# MicroController.net
KiCad netlist of a schematic drawn in Altium Designer
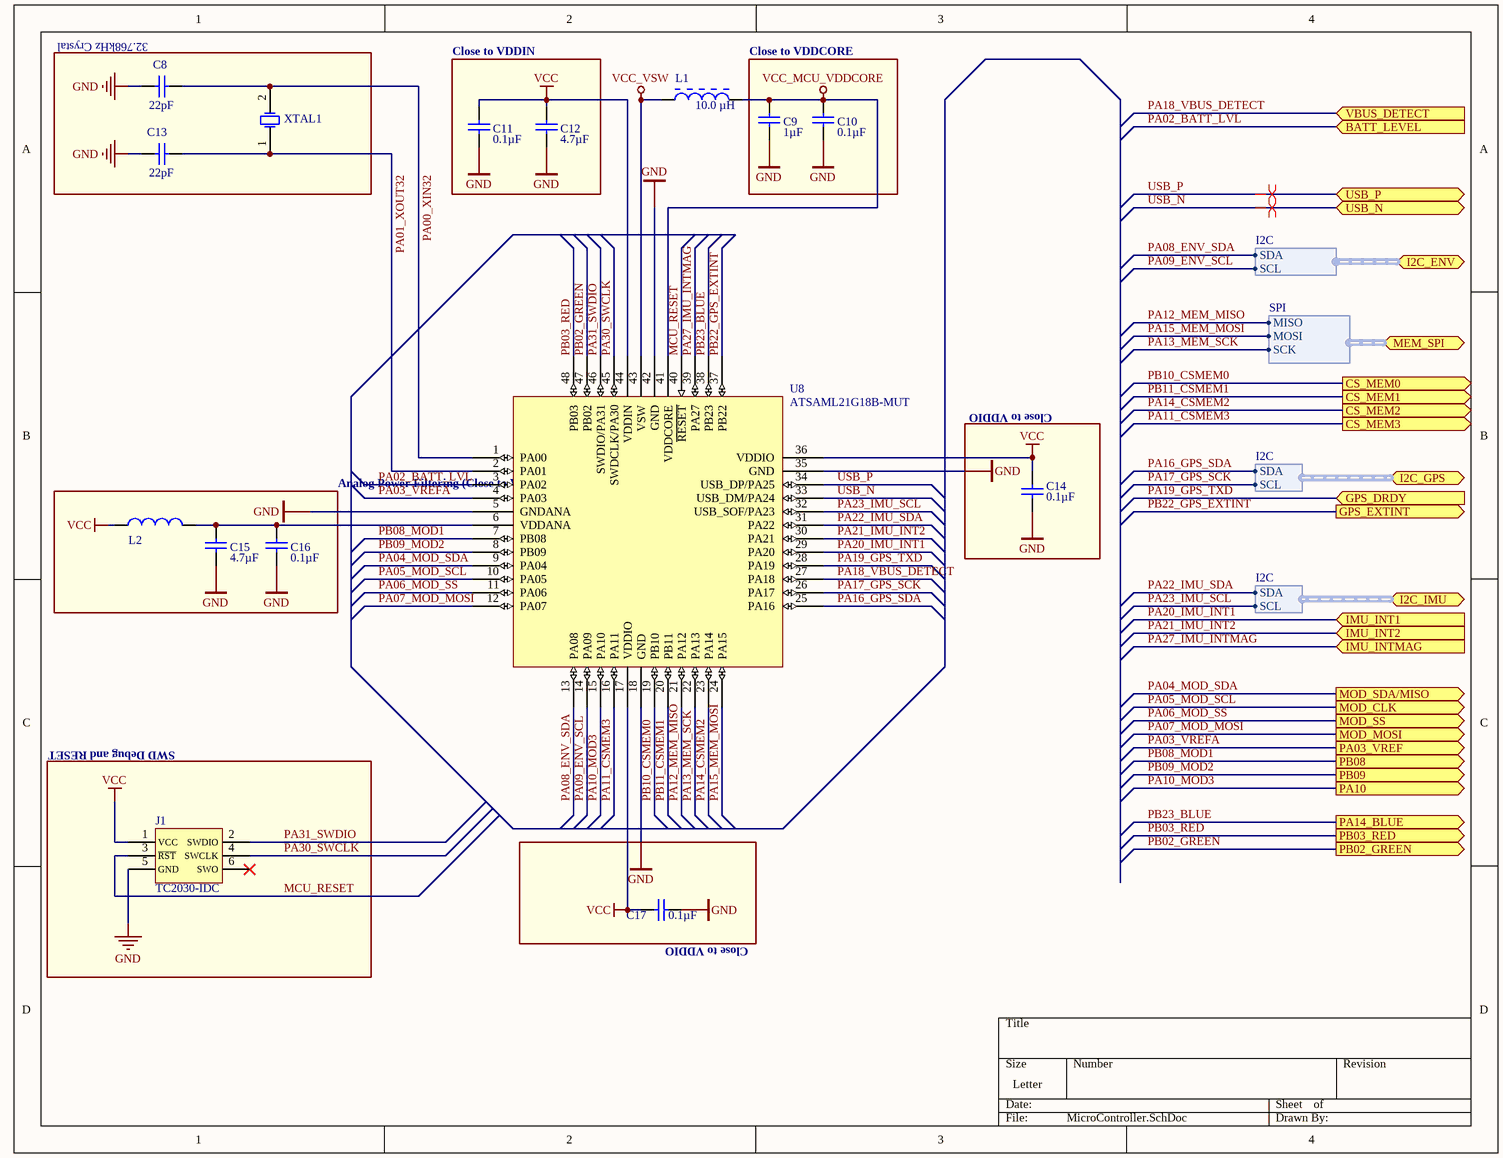
[diagram p0: MicroController.SchDoc]

(export (version "E")
  (design (tool "Eeschema 10.0.6"))
  (components
    (comp (ref "C8")
      (value "GRM1555C1H220FA01D")
      (footprint "C0402M")
      (description "CAP CER 22PF 50V C0G/NP0 0402")
      (fields
        (field (name "HOUSEPART") "NO")
        (field (name "TOLERANCE") "±1%")
        (field (name "CAPACITANCE") "22pF")
      )
      (libsource (lib "MF_Passives") (part "CAPACITOR_NP"))
    )
    (comp (ref "C9")
      (value "CL10B105KP8NFNC")
      (footprint "C0603N")
      (description "CAP CER 1UF 10V X7R 0603")
      (fields
        (field (name "HOUSEPART") "NO")
        (field (name "TOLERANCE") "±10%")
        (field (name "CAPACITANCE") "1µF")
      )
      (libsource (lib "MF_Passives") (part "CAPACITOR_NP"))
    )
    (comp (ref "C10")
      (value "CL10B104KO8NFNC")
      (footprint "C0603N")
      (fields
        (field (name "HOUSEPART") "NO")
        (field (name "TOLERANCE") "±10%")
        (field (name "VOLTAGE") "16V")
        (field (name "CAPACITANCE") "0.1µF")
      )
      (libsource (lib "MF_Passives") (part "CAPACITOR_NP"))
    )
    (comp (ref "C11")
      (value "CL10B104KO8NFNC")
      (footprint "C0603N")
      (fields
        (field (name "HOUSEPART") "NO")
        (field (name "TOLERANCE") "±10%")
        (field (name "VOLTAGE") "16V")
        (field (name "CAPACITANCE") "0.1µF")
      )
      (libsource (lib "MF_Passives") (part "CAPACITOR_NP"))
    )
    (comp (ref "C12")
      (value "C0603C475K8PACTU")
      (footprint "C0603N")
      (description "CAP CER 1UF 10V X7R 0603")
      (fields
        (field (name "HOUSEPART") "NO")
        (field (name "TOLERANCE") "±10%")
        (field (name "CAPACITANCE") "4.7µF")
      )
      (libsource (lib "MF_Passives") (part "CAPACITOR_NP"))
    )
    (comp (ref "C13")
      (value "GRM1555C1H220FA01D")
      (footprint "C0402M")
      (description "CAP CER 22PF 50V C0G/NP0 0402")
      (fields
        (field (name "HOUSEPART") "NO")
        (field (name "TOLERANCE") "±1%")
        (field (name "CAPACITANCE") "22pF")
      )
      (libsource (lib "MF_Passives") (part "CAPACITOR_NP"))
    )
    (comp (ref "C14")
      (value "CL10B104KO8NFNC")
      (footprint "C0603N")
      (fields
        (field (name "HOUSEPART") "NO")
        (field (name "TOLERANCE") "±10%")
        (field (name "VOLTAGE") "16V")
        (field (name "CAPACITANCE") "0.1µF")
      )
      (libsource (lib "MF_Passives") (part "CAPACITOR_NP"))
    )
    (comp (ref "C15")
      (value "C0603C475K8PACTU")
      (footprint "C0603N")
      (description "CAP CER 1UF 10V X7R 0603")
      (fields
        (field (name "HOUSEPART") "NO")
        (field (name "TOLERANCE") "±10%")
        (field (name "CAPACITANCE") "4.7µF")
      )
      (libsource (lib "MF_Passives") (part "CAPACITOR_NP"))
    )
    (comp (ref "C16")
      (value "CL10B104KO8NFNC")
      (footprint "C0603N")
      (fields
        (field (name "HOUSEPART") "NO")
        (field (name "TOLERANCE") "±10%")
        (field (name "VOLTAGE") "16V")
        (field (name "CAPACITANCE") "0.1µF")
      )
      (libsource (lib "MF_Passives") (part "CAPACITOR_NP"))
    )
    (comp (ref "C17")
      (value "CL10B104KO8NFNC")
      (footprint "C0603N")
      (fields
        (field (name "HOUSEPART") "NO")
        (field (name "TOLERANCE") "±10%")
        (field (name "VOLTAGE") "16V")
        (field (name "CAPACITANCE") "0.1µF")
      )
      (libsource (lib "MF_Passives") (part "CAPACITOR_NP"))
    )
    (comp (ref "J1")
      (value "TC2030-IDC")
      (footprint "PINHEAD127_1x5")
      (description "CABLE ADAPTER 6 POS")
      (fields (field (name "MANUFACTURER") "Tag-Connect LLC"))
      (libsource (lib "Connectors") (part "TC2030-IDC-NL"))
    )
    (comp (ref "L1")
      (value "SRN3015-100M")
      (footprint "SRN3015")
      (fields (field (name "INDUCTANCE") "10.0 µH"))
      (libsource (lib "Bourns") (part "CMP-911278-2"))
    )
    (comp (ref "L2")
      (value "LI0603G221R-10")
      (footprint "R0603L")
      (fields (field (name "HOUSEPART") "NO"))
      (libsource (lib "MF_Passives") (part "INDUCTOR"))
    )
    (comp (ref "U8")
      (value "ATSAML21G18B-MUT")
      (footprint "QFN50P700X700X90-49N")
      (libsource (lib "Microchip") (part "ATSAML21G18B-MUT"))
    )
    (comp (ref "XTAL1")
      (value "FC-135 32.7680KA-A3")
      (footprint "FC-135R$2F$FC-135")
      (description "FC-135 Series 32.768 KHz ±20 ppm 12.5 pF -40 to +85°C Surface Mount Crystal")
      (fields (field (name "MANUFACTURER") "epson"))
      (libsource (lib "FC-135R_RC-135") (part "FC-13532.7680KA-A3"))
    )
  )
  (nets
    (net (code "3") (name "/MCU_RESET") (class "Default")
      (node (ref "J1") (pin "3") (pinfunction "~{RST}_3") (pintype "passive"))
      (node (ref "U8") (pin "40") (pinfunction "~{RESET}_40") (pintype "input"))
    )
    (net (code "4") (name "/PA00_XIN32") (class "Default")
      (node (ref "C8") (pin "1") (pinfunction "1_1") (pintype "passive"))
      (node (ref "U8") (pin "1") (pinfunction "PA00_1") (pintype "bidirectional"))
      (node (ref "XTAL1") (pin "2") (pinfunction "X2_2") (pintype "passive"))
    )
    (net (code "5") (name "/PA01_XOUT32") (class "Default")
      (node (ref "C13") (pin "1") (pinfunction "1_1") (pintype "passive"))
      (node (ref "U8") (pin "2") (pinfunction "PA01_2") (pintype "bidirectional"))
      (node (ref "XTAL1") (pin "1") (pinfunction "X1_1") (pintype "passive"))
    )
    (net (code "6") (name "/PA02_BATT_LVL") (class "Default")
      (node (ref "U8") (pin "3") (pinfunction "PA02_3") (pintype "bidirectional"))
    )
    (net (code "7") (name "/PA03_VREFA") (class "Default")
      (node (ref "U8") (pin "4") (pinfunction "PA03_4") (pintype "bidirectional"))
    )
    (net (code "8") (name "/PA04_MOD_SDA") (class "Default")
      (node (ref "U8") (pin "9") (pinfunction "PA04_9") (pintype "bidirectional"))
    )
    (net (code "9") (name "/PA05_MOD_SCL") (class "Default")
      (node (ref "U8") (pin "10") (pinfunction "PA05_10") (pintype "bidirectional"))
    )
    (net (code "10") (name "/PA06_MOD_SS") (class "Default")
      (node (ref "U8") (pin "11") (pinfunction "PA06_11") (pintype "bidirectional"))
    )
    (net (code "11") (name "/PA07_MOD_MOSI") (class "Default")
      (node (ref "U8") (pin "12") (pinfunction "PA07_12") (pintype "bidirectional"))
    )
    (net (code "12") (name "/PA08_ENV_SDA") (class "Default")
      (node (ref "U8") (pin "13") (pinfunction "PA08_13") (pintype "bidirectional"))
    )
    (net (code "13") (name "/PA09_ENV_SCL") (class "Default")
      (node (ref "U8") (pin "14") (pinfunction "PA09_14") (pintype "bidirectional"))
    )
    (net (code "14") (name "/PA10_MOD3") (class "Default")
      (node (ref "U8") (pin "15") (pinfunction "PA10_15") (pintype "bidirectional"))
    )
    (net (code "15") (name "/PA11_CSMEM3") (class "Default")
      (node (ref "U8") (pin "16") (pinfunction "PA11_16") (pintype "bidirectional"))
    )
    (net (code "16") (name "/PA12_MEM_MISO") (class "Default")
      (node (ref "U8") (pin "21") (pinfunction "PA12_21") (pintype "bidirectional"))
    )
    (net (code "17") (name "/PA13_MEM_SCK") (class "Default")
      (node (ref "U8") (pin "22") (pinfunction "PA13_22") (pintype "bidirectional"))
    )
    (net (code "18") (name "/PA14_CSMEM2") (class "Default")
      (node (ref "U8") (pin "23") (pinfunction "PA14_23") (pintype "bidirectional"))
    )
    (net (code "19") (name "/PA15_MEM_MOSI") (class "Default")
      (node (ref "U8") (pin "24") (pinfunction "PA15_24") (pintype "bidirectional"))
    )
    (net (code "20") (name "/PA16_GPS_SDA") (class "Default")
      (node (ref "U8") (pin "25") (pinfunction "PA16_25") (pintype "bidirectional"))
    )
    (net (code "21") (name "/PA17_GPS_SCK") (class "Default")
      (node (ref "U8") (pin "26") (pinfunction "PA17_26") (pintype "bidirectional"))
    )
    (net (code "22") (name "/PA18_VBUS_DETECT") (class "Default")
      (node (ref "U8") (pin "27") (pinfunction "PA18_27") (pintype "bidirectional"))
    )
    (net (code "23") (name "/PA19_GPS_TXD") (class "Default")
      (node (ref "U8") (pin "28") (pinfunction "PA19_28") (pintype "bidirectional"))
    )
    (net (code "24") (name "/PA20_IMU_INT1") (class "Default")
      (node (ref "U8") (pin "29") (pinfunction "PA20_29") (pintype "bidirectional"))
    )
    (net (code "25") (name "/PA21_IMU_INT2") (class "Default")
      (node (ref "U8") (pin "30") (pinfunction "PA21_30") (pintype "bidirectional"))
    )
    (net (code "26") (name "/PA22_IMU_SDA") (class "Default")
      (node (ref "U8") (pin "31") (pinfunction "PA22_31") (pintype "bidirectional"))
    )
    (net (code "27") (name "/PA23_IMU_SCL") (class "Default")
      (node (ref "U8") (pin "32") (pinfunction "USB_SOF/PA23_32") (pintype "bidirectional"))
    )
    (net (code "28") (name "/PA27_IMU_INTMAG") (class "Default")
      (node (ref "U8") (pin "39") (pinfunction "PA27_39") (pintype "bidirectional"))
    )
    (net (code "29") (name "/PA30_SWCLK") (class "Default")
      (node (ref "J1") (pin "4") (pinfunction "SWCLK_4") (pintype "passive"))
      (node (ref "U8") (pin "45") (pinfunction "SWDCLK/PA30_45") (pintype "bidirectional"))
    )
    (net (code "30") (name "/PA31_SWDIO") (class "Default")
      (node (ref "J1") (pin "2") (pinfunction "SWDIO_2") (pintype "passive"))
      (node (ref "U8") (pin "46") (pinfunction "SWDIO/PA31_46") (pintype "bidirectional"))
    )
    (net (code "31") (name "/PB02_GREEN") (class "Default")
      (node (ref "U8") (pin "47") (pinfunction "PB02_47") (pintype "bidirectional"))
    )
    (net (code "32") (name "/PB03_RED") (class "Default")
      (node (ref "U8") (pin "48") (pinfunction "PB03_48") (pintype "bidirectional"))
    )
    (net (code "33") (name "/PB08_MOD1") (class "Default")
      (node (ref "U8") (pin "7") (pinfunction "PB08_7") (pintype "bidirectional"))
    )
    (net (code "34") (name "/PB09_MOD2") (class "Default")
      (node (ref "U8") (pin "8") (pinfunction "PB09_8") (pintype "bidirectional"))
    )
    (net (code "35") (name "/PB10_CSMEM0") (class "Default")
      (node (ref "U8") (pin "19") (pinfunction "PB10_19") (pintype "bidirectional"))
    )
    (net (code "36") (name "/PB11_CSMEM1") (class "Default")
      (node (ref "U8") (pin "20") (pinfunction "PB11_20") (pintype "bidirectional"))
    )
    (net (code "37") (name "/PB22_GPS_EXTINT") (class "Default")
      (node (ref "U8") (pin "37") (pinfunction "PB22_37") (pintype "bidirectional"))
    )
    (net (code "38") (name "/PB23_BLUE") (class "Default")
      (node (ref "U8") (pin "38") (pinfunction "PB23_38") (pintype "bidirectional"))
    )
    (net (code "39") (name "/USB_N") (class "Default")
      (node (ref "U8") (pin "33") (pinfunction "USB_DM/PA24_33") (pintype "bidirectional"))
    )
    (net (code "40") (name "/USB_P") (class "Default")
      (node (ref "U8") (pin "34") (pinfunction "USB_DP/PA25_34") (pintype "bidirectional"))
    )
    (net (code "43") (name "GND") (class "Default")
      (node (ref "C10") (pin "2") (pinfunction "2_2") (pintype "passive"))
      (node (ref "C11") (pin "2") (pinfunction "2_2") (pintype "passive"))
      (node (ref "C12") (pin "1") (pinfunction "1_1") (pintype "passive"))
      (node (ref "C13") (pin "2") (pinfunction "2_2") (pintype "passive"))
      (node (ref "C14") (pin "2") (pinfunction "2_2") (pintype "passive"))
      (node (ref "C15") (pin "1") (pinfunction "1_1") (pintype "passive"))
      (node (ref "C16") (pin "2") (pinfunction "2_2") (pintype "passive"))
      (node (ref "C17") (pin "2") (pinfunction "2_2") (pintype "passive"))
      (node (ref "C8") (pin "2") (pinfunction "2_2") (pintype "passive"))
      (node (ref "C9") (pin "1") (pinfunction "1_1") (pintype "passive"))
      (node (ref "J1") (pin "5") (pinfunction "GND_5") (pintype "passive"))
      (node (ref "U8") (pin "18") (pinfunction "GND_18") (pintype "passive"))
      (node (ref "U8") (pin "35") (pinfunction "GND_35") (pintype "passive"))
      (node (ref "U8") (pin "42") (pinfunction "GND_42") (pintype "passive"))
      (node (ref "U8") (pin "5") (pinfunction "GNDANA_5") (pintype "passive"))
    )
    (net (code "44") (name "Net-(U8-VDDANA)") (class "Default")
      (node (ref "C15") (pin "2") (pinfunction "2_2") (pintype "passive"))
      (node (ref "C16") (pin "1") (pinfunction "1_1") (pintype "passive"))
      (node (ref "L2") (pin "2") (pinfunction "2_2") (pintype "passive"))
      (node (ref "U8") (pin "6") (pinfunction "VDDANA_6") (pintype "power_in"))
    )
    (net (code "45") (name "VCC") (class "Default")
      (node (ref "C11") (pin "1") (pinfunction "1_1") (pintype "passive"))
      (node (ref "C12") (pin "2") (pinfunction "2_2") (pintype "passive"))
      (node (ref "C14") (pin "1") (pinfunction "1_1") (pintype "passive"))
      (node (ref "C17") (pin "1") (pinfunction "1_1") (pintype "passive"))
      (node (ref "J1") (pin "1") (pinfunction "VCC_1") (pintype "passive"))
      (node (ref "L2") (pin "1") (pinfunction "1_1") (pintype "passive"))
      (node (ref "U8") (pin "17") (pinfunction "VDDIO_17") (pintype "power_in"))
      (node (ref "U8") (pin "36") (pinfunction "VDDIO_36") (pintype "power_in"))
      (node (ref "U8") (pin "44") (pinfunction "VDDIN_44") (pintype "power_in"))
    )
    (net (code "46") (name "VCC_MCU_VDDCORE") (class "Default")
      (node (ref "C10") (pin "1") (pinfunction "1_1") (pintype "passive"))
      (node (ref "C9") (pin "2") (pinfunction "2_2") (pintype "passive"))
      (node (ref "L1") (pin "2") (pinfunction "2_2") (pintype "passive"))
      (node (ref "U8") (pin "41") (pinfunction "VDDCORE_41") (pintype "power_in"))
    )
    (net (code "47") (name "VCC_VSW") (class "Default")
      (node (ref "L1") (pin "1") (pinfunction "1_1") (pintype "passive"))
      (node (ref "U8") (pin "43") (pinfunction "VSW_43") (pintype "power_in"))
    )
    (net (code "48") (name "unconnected-(J1-SWO-Pad6)") (class "Default")
      (node (ref "J1") (pin "6") (pinfunction "SWO_6") (pintype "passive+no_connect"))
    )
  )
)
